# volume_control.net
KiCad netlist of a schematic drawn in EAGLE
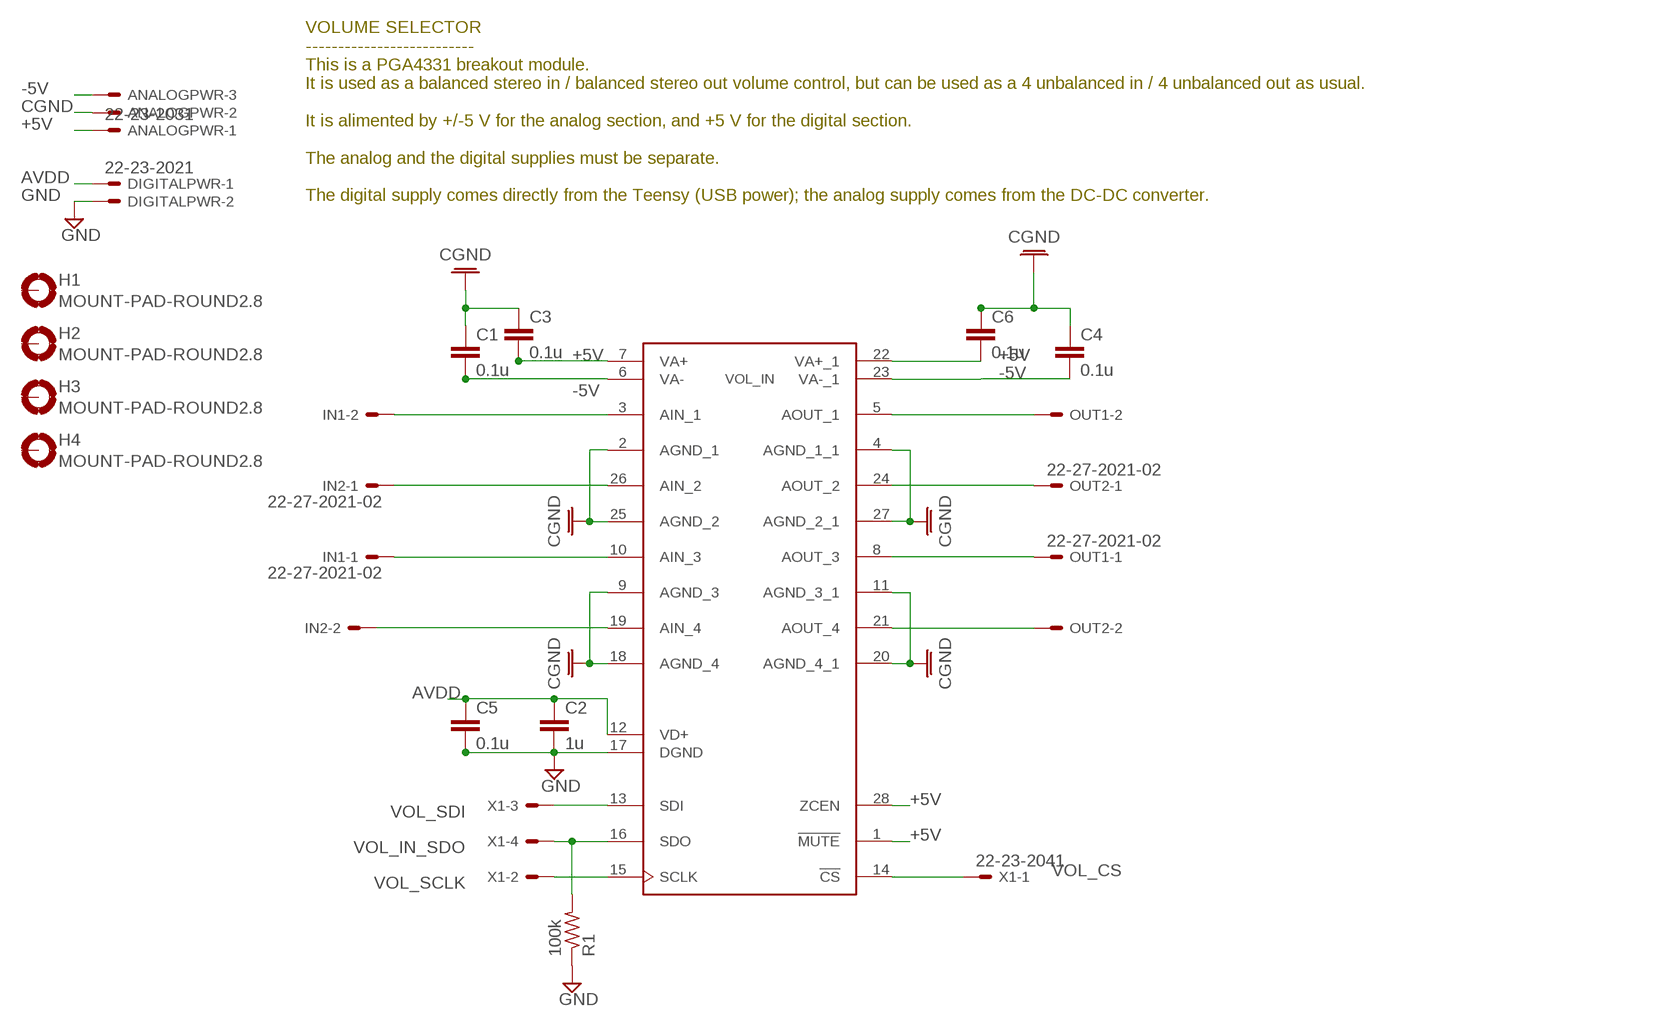
[diagram p0: schematic, sheet 1]

(export (version "E")
  (design (tool "Eeschema 10.0.6"))
  (components
    (comp (ref "ANALOGPWR")
      (value "22-23-2031")
      (footprint "eagle-import:22-23-2031")
      (fields (field (name "MF") "MOLEX"))
      (libsource (lib "eagle-import") (part "22-23-2031"))
    )
    (comp (ref "C1")
      (value "0.1u")
      (footprint "eagle-import:C0603")
      (libsource (lib "eagle-import") (part "C-EUC0603"))
    )
    (comp (ref "C2")
      (value "1u")
      (footprint "eagle-import:C0603")
      (libsource (lib "eagle-import") (part "C-EUC0603"))
    )
    (comp (ref "C3")
      (value "0.1u")
      (footprint "eagle-import:C0603")
      (libsource (lib "eagle-import") (part "C-EUC0603"))
    )
    (comp (ref "C4")
      (value "0.1u")
      (footprint "eagle-import:C0603")
      (libsource (lib "eagle-import") (part "C-EUC0603"))
    )
    (comp (ref "C5")
      (value "0.1u")
      (footprint "eagle-import:C0603")
      (libsource (lib "eagle-import") (part "C-EUC0603"))
    )
    (comp (ref "C6")
      (value "0.1u")
      (footprint "eagle-import:C0603")
      (libsource (lib "eagle-import") (part "C-EUC0603"))
    )
    (comp (ref "DIGITALPWR")
      (value "22-23-2021")
      (footprint "eagle-import:22-23-2021")
      (fields (field (name "MF") "MOLEX"))
      (libsource (lib "eagle-import") (part "22-23-2021"))
    )
    (comp (ref "H1")
      (value "MOUNT-PAD-ROUND2.8")
      (footprint "eagle-import:2,8-PAD")
      (libsource (lib "eagle-import") (part "MOUNT-PAD-ROUND2.8"))
    )
    (comp (ref "H2")
      (value "MOUNT-PAD-ROUND2.8")
      (footprint "eagle-import:2,8-PAD")
      (libsource (lib "eagle-import") (part "MOUNT-PAD-ROUND2.8"))
    )
    (comp (ref "H3")
      (value "MOUNT-PAD-ROUND2.8")
      (footprint "eagle-import:2,8-PAD")
      (libsource (lib "eagle-import") (part "MOUNT-PAD-ROUND2.8"))
    )
    (comp (ref "H4")
      (value "MOUNT-PAD-ROUND2.8")
      (footprint "eagle-import:2,8-PAD")
      (libsource (lib "eagle-import") (part "MOUNT-PAD-ROUND2.8"))
    )
    (comp (ref "IN1")
      (value "22-27-2021-02")
      (footprint "eagle-import:6410-02")
      (libsource (lib "eagle-import") (part "22-?-0227-2021"))
    )
    (comp (ref "IN2")
      (value "22-27-2021-02")
      (footprint "eagle-import:6410-02")
      (libsource (lib "eagle-import") (part "22-?-0227-2021"))
    )
    (comp (ref "OUT1")
      (value "22-27-2021-02")
      (footprint "eagle-import:6410-02")
      (libsource (lib "eagle-import") (part "22-?-0227-2021"))
    )
    (comp (ref "OUT2")
      (value "22-27-2021-02")
      (footprint "eagle-import:6410-02")
      (libsource (lib "eagle-import") (part "22-?-0227-2021"))
    )
    (comp (ref "R1")
      (value "100k")
      (footprint "eagle-import:R0603")
      (libsource (lib "eagle-import") (part "R-US_R0603"))
    )
    (comp (ref "VOL_IN")
      (value "PGA4311")
      (footprint "eagle-import:DW_R-PDSO_G28")
      (libsource (lib "eagle-import") (part "PGA4311"))
    )
    (comp (ref "X1")
      (value "22-23-2041")
      (footprint "eagle-import:22-23-2041")
      (fields (field (name "MF") "MOLEX"))
      (libsource (lib "eagle-import") (part "22-23-2041"))
    )
  )
  (nets
    (net (code "1") (name "/+5V") (class "Default")
      (node (ref "ANALOGPWR") (pin "1") (pinfunction "S_1") (pintype "passive"))
      (node (ref "C3") (pin "2") (pinfunction "2_2") (pintype "passive"))
      (node (ref "C6") (pin "2") (pinfunction "2_2") (pintype "passive"))
      (node (ref "VOL_IN") (pin "1") (pinfunction "~{MUTE}_1") (pintype "input"))
      (node (ref "VOL_IN") (pin "22") (pinfunction "VA+_1_22") (pintype "power_in"))
      (node (ref "VOL_IN") (pin "28") (pinfunction "ZCEN_28") (pintype "input"))
      (node (ref "VOL_IN") (pin "7") (pinfunction "VA+_7") (pintype "power_in"))
    )
    (net (code "2") (name "/-5V") (class "Default")
      (node (ref "ANALOGPWR") (pin "3") (pinfunction "S_3") (pintype "passive"))
      (node (ref "C1") (pin "2") (pinfunction "2_2") (pintype "passive"))
      (node (ref "C4") (pin "2") (pinfunction "2_2") (pintype "passive"))
      (node (ref "VOL_IN") (pin "23") (pinfunction "VA-_1_23") (pintype "power_in"))
      (node (ref "VOL_IN") (pin "6") (pinfunction "VA-_6") (pintype "power_in"))
    )
    (net (code "3") (name "/AVDD") (class "Default")
      (node (ref "C2") (pin "1") (pinfunction "1_1") (pintype "passive"))
      (node (ref "C5") (pin "1") (pinfunction "1_1") (pintype "passive"))
      (node (ref "DIGITALPWR") (pin "1") (pinfunction "S_1") (pintype "passive"))
      (node (ref "VOL_IN") (pin "12") (pinfunction "VD+_12") (pintype "power_in"))
    )
    (net (code "4") (name "/VOL_CS") (class "Default")
      (node (ref "VOL_IN") (pin "14") (pinfunction "~{CS}_14") (pintype "input"))
      (node (ref "X1") (pin "1") (pinfunction "S_1") (pintype "passive"))
    )
    (net (code "5") (name "/VOL_IN_SDO") (class "Default")
      (node (ref "R1") (pin "2") (pinfunction "2_2") (pintype "passive"))
      (node (ref "VOL_IN") (pin "16") (pinfunction "SDO_16") (pintype "output"))
      (node (ref "X1") (pin "4") (pinfunction "S_4") (pintype "passive"))
    )
    (net (code "6") (name "/VOL_SCLK") (class "Default")
      (node (ref "VOL_IN") (pin "15") (pinfunction "SCLK_15") (pintype "input"))
      (node (ref "X1") (pin "2") (pinfunction "S_2") (pintype "passive"))
    )
    (net (code "7") (name "/VOL_SDI") (class "Default")
      (node (ref "VOL_IN") (pin "13") (pinfunction "SDI_13") (pintype "input"))
      (node (ref "X1") (pin "3") (pinfunction "S_3") (pintype "passive"))
    )
    (net (code "8") (name "CGND") (class "Default")
      (node (ref "ANALOGPWR") (pin "2") (pinfunction "S_2") (pintype "passive"))
      (node (ref "C1") (pin "1") (pinfunction "1_1") (pintype "passive"))
      (node (ref "C3") (pin "1") (pinfunction "1_1") (pintype "passive"))
      (node (ref "C4") (pin "1") (pinfunction "1_1") (pintype "passive"))
      (node (ref "C6") (pin "1") (pinfunction "1_1") (pintype "passive"))
      (node (ref "VOL_IN") (pin "11") (pinfunction "AGND_3_1_11") (pintype "power_in"))
      (node (ref "VOL_IN") (pin "18") (pinfunction "AGND_4_18") (pintype "power_in"))
      (node (ref "VOL_IN") (pin "2") (pinfunction "AGND_1_2") (pintype "power_in"))
      (node (ref "VOL_IN") (pin "20") (pinfunction "AGND_4_1_20") (pintype "power_in"))
      (node (ref "VOL_IN") (pin "25") (pinfunction "AGND_2_25") (pintype "power_in"))
      (node (ref "VOL_IN") (pin "27") (pinfunction "AGND_2_1_27") (pintype "power_in"))
      (node (ref "VOL_IN") (pin "4") (pinfunction "AGND_1_1_4") (pintype "power_in"))
      (node (ref "VOL_IN") (pin "9") (pinfunction "AGND_3_9") (pintype "power_in"))
    )
    (net (code "9") (name "GND") (class "Default")
      (node (ref "C2") (pin "2") (pinfunction "2_2") (pintype "passive"))
      (node (ref "C5") (pin "2") (pinfunction "2_2") (pintype "passive"))
      (node (ref "DIGITALPWR") (pin "2") (pinfunction "S_2") (pintype "passive"))
      (node (ref "R1") (pin "1") (pinfunction "1_1") (pintype "passive"))
      (node (ref "VOL_IN") (pin "17") (pinfunction "DGND_17") (pintype "power_in"))
    )
    (net (code "10") (name "Net-(IN1A-S)") (class "Default")
      (node (ref "IN1") (pin "1") (pinfunction "S_1") (pintype "passive"))
      (node (ref "VOL_IN") (pin "10") (pinfunction "AIN_3_10") (pintype "input"))
    )
    (net (code "11") (name "Net-(IN1B-S)") (class "Default")
      (node (ref "IN1") (pin "2") (pinfunction "S_2") (pintype "passive"))
      (node (ref "VOL_IN") (pin "3") (pinfunction "AIN_1_3") (pintype "bidirectional"))
    )
    (net (code "12") (name "Net-(IN2A-S)") (class "Default")
      (node (ref "IN2") (pin "1") (pinfunction "S_1") (pintype "passive"))
      (node (ref "VOL_IN") (pin "26") (pinfunction "AIN_2_26") (pintype "input"))
    )
    (net (code "13") (name "Net-(IN2B-S)") (class "Default")
      (node (ref "IN2") (pin "2") (pinfunction "S_2") (pintype "passive"))
      (node (ref "VOL_IN") (pin "19") (pinfunction "AIN_4_19") (pintype "input"))
    )
    (net (code "14") (name "Net-(OUT1A-S)") (class "Default")
      (node (ref "OUT1") (pin "1") (pinfunction "S_1") (pintype "passive"))
      (node (ref "VOL_IN") (pin "8") (pinfunction "AOUT_3_8") (pintype "output"))
    )
    (net (code "15") (name "Net-(OUT1B-S)") (class "Default")
      (node (ref "OUT1") (pin "2") (pinfunction "S_2") (pintype "passive"))
      (node (ref "VOL_IN") (pin "5") (pinfunction "AOUT_1_5") (pintype "bidirectional"))
    )
    (net (code "16") (name "Net-(OUT2A-S)") (class "Default")
      (node (ref "OUT2") (pin "1") (pinfunction "S_1") (pintype "passive"))
      (node (ref "VOL_IN") (pin "24") (pinfunction "AOUT_2_24") (pintype "output"))
    )
    (net (code "17") (name "Net-(OUT2B-S)") (class "Default")
      (node (ref "OUT2") (pin "2") (pinfunction "S_2") (pintype "passive"))
      (node (ref "VOL_IN") (pin "21") (pinfunction "AOUT_4_21") (pintype "output"))
    )
    (net (code "18") (name "unconnected-(H1-MOUNT-PadB2,8)") (class "Default")
      (node (ref "H1") (pin "B2,8") (pinfunction "MOUNT_B2,8") (pintype "passive"))
    )
    (net (code "19") (name "unconnected-(H2-MOUNT-PadB2,8)") (class "Default")
      (node (ref "H2") (pin "B2,8") (pinfunction "MOUNT_B2,8") (pintype "passive"))
    )
    (net (code "20") (name "unconnected-(H3-MOUNT-PadB2,8)") (class "Default")
      (node (ref "H3") (pin "B2,8") (pinfunction "MOUNT_B2,8") (pintype "passive"))
    )
    (net (code "21") (name "unconnected-(H4-MOUNT-PadB2,8)") (class "Default")
      (node (ref "H4") (pin "B2,8") (pinfunction "MOUNT_B2,8") (pintype "passive"))
    )
  )
)
